# Servo_Control_Board.net
KiCad netlist of a schematic drawn in Altium Designer
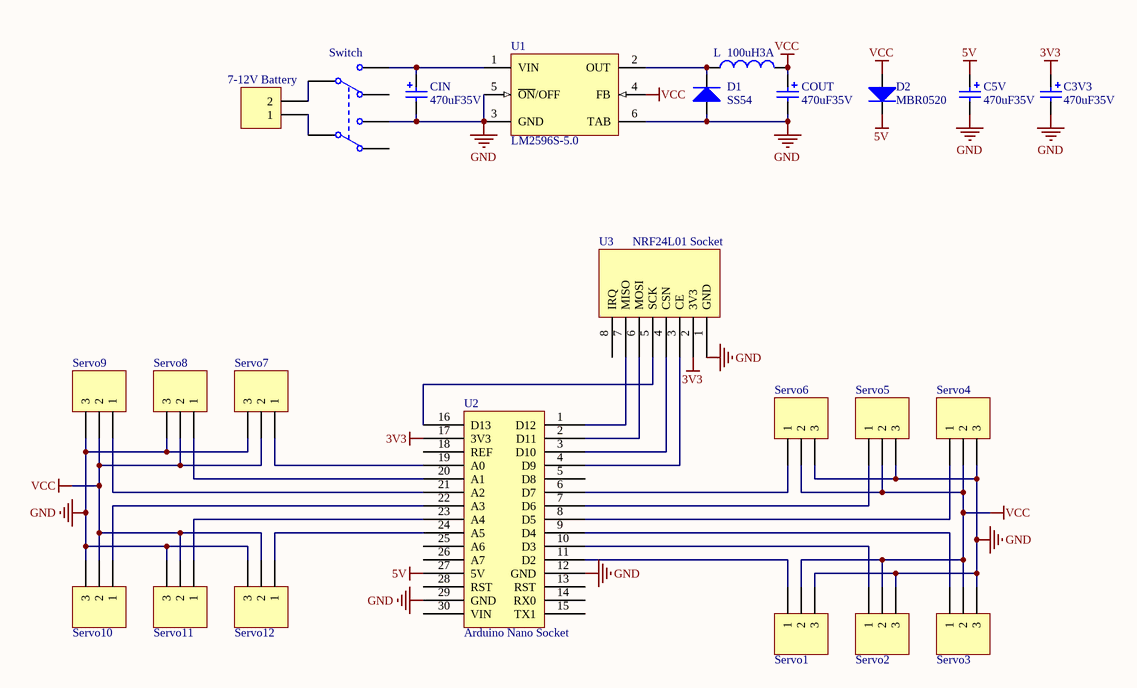
[diagram p0: Servo Control Board.SchDoc]

(export (version "E")
  (design (tool "Eeschema 10.0.6"))
  (components
    (comp (ref "7-12V Battery")
      (value "Header 2")
      (footprint "KF301-2P")
      (libsource (lib "Customer_Library") (part "Header 2"))
    )
    (comp (ref "C3V3")
      (value "470uF35V")
      (footprint "cp10x10")
      (fields (field (name "Comment") "Cap Pol"))
      (libsource (lib "Customer_Library") (part "Cap Pol"))
    )
    (comp (ref "C5V")
      (value "470uF35V")
      (footprint "cp10x10")
      (fields (field (name "Comment") "Cap Pol"))
      (libsource (lib "Customer_Library") (part "Cap Pol"))
    )
    (comp (ref "CIN")
      (value "470uF35V")
      (footprint "cp10x10")
      (fields (field (name "Comment") "Cap Pol"))
      (libsource (lib "Customer_Library") (part "Cap Pol"))
    )
    (comp (ref "COUT")
      (value "470uF35V")
      (footprint "cp10x10")
      (fields (field (name "Comment") "Cap Pol"))
      (libsource (lib "Customer_Library") (part "Cap Pol"))
    )
    (comp (ref "D1") (value "SS54") (footprint "SS54") (libsource (lib "Customer_Library") (part "Diode")))
    (comp (ref "D2")
      (value "MBR0520")
      (footprint "SOD-123")
      (libsource (lib "Customer_Library") (part "Diode"))
    )
    (comp (ref "L")
      (value "100uH3A")
      (footprint "Inductor 14.6x6.8x0.8")
      (fields (field (name "Comment") "Inductor"))
      (libsource (lib "Customer_Library") (part "Inductor"))
    )
    (comp (ref "Servo1") (value "Header 3") (footprint "Header 3") (libsource (lib "") (part "Header 3_3")))
    (comp (ref "Servo2") (value "Header 3") (footprint "Header 3") (libsource (lib "") (part "Header 3_3")))
    (comp (ref "Servo3") (value "Header 3") (footprint "Header 3") (libsource (lib "") (part "Header 3_3")))
    (comp (ref "Servo4")
      (value "Header 3")
      (footprint "Header 3")
      (libsource (lib "Customer_Library") (part "Header 3"))
    )
    (comp (ref "Servo5")
      (value "Header 3")
      (footprint "Header 3")
      (libsource (lib "Customer_Library") (part "Header 3"))
    )
    (comp (ref "Servo6")
      (value "Header 3")
      (footprint "Header 3")
      (libsource (lib "Customer_Library") (part "Header 3"))
    )
    (comp (ref "Servo7") (value "Header 3") (footprint "Header 3") (libsource (lib "") (part "Header 3_2")))
    (comp (ref "Servo8") (value "Header 3") (footprint "Header 3") (libsource (lib "") (part "Header 3_2")))
    (comp (ref "Servo9") (value "Header 3") (footprint "Header 3") (libsource (lib "") (part "Header 3_2")))
    (comp (ref "Servo10") (value "Header 3") (footprint "Header 3") (libsource (lib "") (part "Header 3_1")))
    (comp (ref "Servo11") (value "Header 3") (footprint "Header 3") (libsource (lib "") (part "Header 3_1")))
    (comp (ref "Servo12") (value "Header 3") (footprint "Header 3") (libsource (lib "") (part "Header 3_1")))
    (comp (ref "Switch")
      (value "Push Switch")
      (footprint "Push Switch 7x7")
      (libsource (lib "Customer_Library") (part "Push Switch"))
    )
    (comp (ref "U1")
      (value "LM2596S-5.0")
      (footprint "TS5B_N")
      (description "SIMPLE SWITCHER Power Converter 150 KHz 3A Step-Down Voltage Regulator")
      (fields
        (field (name "MANUFACTURER") "National Semiconductor")
        (field (name "DIGIKEYPARTNUMBER") "LM2596S-5.0-ND")
        (field (name "PUBLISHER") "Altium Limited")
      )
      (libsource (lib "NSC Switcher") (part "LM2596S-5.0"))
    )
    (comp (ref "U2")
      (value "Arduino Nano Socket")
      (footprint "arduino nano socket")
      (libsource (lib "Customer_Library") (part "Arduino Nano Socket"))
    )
    (comp (ref "U3")
      (value "NRF24L01 Socket")
      (footprint "nrf24l01 socket")
      (libsource (lib "Customer_Library") (part "NRF24L01 Socket"))
    )
  )
  (nets
    (net (code "1") (name "3V3") (class "Default")
      (node (ref "C3V3") (pin "1") (pinfunction "1_1") (pintype "passive"))
      (node (ref "U2") (pin "17") (pinfunction "3V3_17") (pintype "passive"))
      (node (ref "U3") (pin "2") (pinfunction "3V3_2") (pintype "passive"))
    )
    (net (code "2") (name "5V") (class "Default")
      (node (ref "C5V") (pin "1") (pinfunction "1_1") (pintype "passive"))
      (node (ref "D2") (pin "2") (pinfunction "K_2") (pintype "passive"))
      (node (ref "U2") (pin "27") (pinfunction "5V_27") (pintype "passive"))
    )
    (net (code "3") (name "GND") (class "Default")
      (node (ref "C3V3") (pin "2") (pinfunction "2_2") (pintype "passive"))
      (node (ref "C5V") (pin "2") (pinfunction "2_2") (pintype "passive"))
      (node (ref "CIN") (pin "2") (pinfunction "2_2") (pintype "passive"))
      (node (ref "COUT") (pin "2") (pinfunction "2_2") (pintype "passive"))
      (node (ref "D1") (pin "1") (pinfunction "A_1") (pintype "passive"))
      (node (ref "Servo1") (pin "3") (pinfunction "3_3") (pintype "passive"))
      (node (ref "Servo10") (pin "3") (pinfunction "3_3") (pintype "passive"))
      (node (ref "Servo11") (pin "3") (pinfunction "3_3") (pintype "passive"))
      (node (ref "Servo12") (pin "3") (pinfunction "3_3") (pintype "passive"))
      (node (ref "Servo2") (pin "3") (pinfunction "3_3") (pintype "passive"))
      (node (ref "Servo3") (pin "3") (pinfunction "3_3") (pintype "passive"))
      (node (ref "Servo4") (pin "3") (pinfunction "3_3") (pintype "passive"))
      (node (ref "Servo5") (pin "3") (pinfunction "3_3") (pintype "passive"))
      (node (ref "Servo6") (pin "3") (pinfunction "3_3") (pintype "passive"))
      (node (ref "Servo7") (pin "3") (pinfunction "3_3") (pintype "passive"))
      (node (ref "Servo8") (pin "3") (pinfunction "3_3") (pintype "passive"))
      (node (ref "Servo9") (pin "3") (pinfunction "3_3") (pintype "passive"))
      (node (ref "Switch") (pin "3") (pinfunction "NO1_3") (pintype "passive"))
      (node (ref "U1") (pin "3") (pinfunction "GND_3") (pintype "power_in"))
      (node (ref "U1") (pin "5") (pinfunction "~{ON}/OFF_5") (pintype "input"))
      (node (ref "U1") (pin "6") (pinfunction "TAB_6") (pintype "power_in"))
      (node (ref "U2") (pin "12") (pinfunction "GND_12") (pintype "passive"))
      (node (ref "U2") (pin "29") (pinfunction "GND_29") (pintype "passive"))
      (node (ref "U3") (pin "1") (pinfunction "GND_1") (pintype "passive"))
    )
    (net (code "4") (name "Net-(D1-K)") (class "Default")
      (node (ref "D1") (pin "2") (pinfunction "K_2") (pintype "passive"))
      (node (ref "L") (pin "1") (pinfunction "1_1") (pintype "passive"))
      (node (ref "U1") (pin "2") (pinfunction "OUT_2") (pintype "power_in"))
    )
    (net (code "5") (name "Net-(Switch-COMMON1)") (class "Default")
      (node (ref "7-12V Battery") (pin "1") (pinfunction "1_1") (pintype "passive"))
      (node (ref "Switch") (pin "1") (pinfunction "COMMON1_1") (pintype "passive"))
    )
    (net (code "6") (name "Net-(Switch-COMMON2)") (class "Default")
      (node (ref "7-12V Battery") (pin "2") (pinfunction "2_2") (pintype "passive"))
      (node (ref "Switch") (pin "4") (pinfunction "COMMON2_4") (pintype "passive"))
    )
    (net (code "7") (name "Net-(Switch-NO2)") (class "Default")
      (node (ref "CIN") (pin "1") (pinfunction "1_1") (pintype "passive"))
      (node (ref "Switch") (pin "6") (pinfunction "NO2_6") (pintype "passive"))
      (node (ref "U1") (pin "1") (pinfunction "VIN_1") (pintype "power_in"))
    )
    (net (code "8") (name "Net-(U2-A0)") (class "Default")
      (node (ref "Servo7") (pin "1") (pinfunction "1_1") (pintype "passive"))
      (node (ref "U2") (pin "19") (pinfunction "A0_19") (pintype "passive"))
    )
    (net (code "9") (name "Net-(U2-A1)") (class "Default")
      (node (ref "Servo8") (pin "1") (pinfunction "1_1") (pintype "passive"))
      (node (ref "U2") (pin "20") (pinfunction "A1_20") (pintype "passive"))
    )
    (net (code "10") (name "Net-(U2-A2)") (class "Default")
      (node (ref "Servo9") (pin "1") (pinfunction "1_1") (pintype "passive"))
      (node (ref "U2") (pin "21") (pinfunction "A2_21") (pintype "passive"))
    )
    (net (code "11") (name "Net-(U2-A3)") (class "Default")
      (node (ref "Servo10") (pin "1") (pinfunction "1_1") (pintype "passive"))
      (node (ref "U2") (pin "22") (pinfunction "A3_22") (pintype "passive"))
    )
    (net (code "12") (name "Net-(U2-A4)") (class "Default")
      (node (ref "Servo11") (pin "1") (pinfunction "1_1") (pintype "passive"))
      (node (ref "U2") (pin "23") (pinfunction "A4_23") (pintype "passive"))
    )
    (net (code "13") (name "Net-(U2-A5)") (class "Default")
      (node (ref "Servo12") (pin "1") (pinfunction "1_1") (pintype "passive"))
      (node (ref "U2") (pin "24") (pinfunction "A5_24") (pintype "passive"))
    )
    (net (code "14") (name "Net-(U2-D2)") (class "Default")
      (node (ref "Servo1") (pin "1") (pinfunction "1_1") (pintype "passive"))
      (node (ref "U2") (pin "11") (pinfunction "D2_11") (pintype "passive"))
    )
    (net (code "15") (name "Net-(U2-D3)") (class "Default")
      (node (ref "Servo2") (pin "1") (pinfunction "1_1") (pintype "passive"))
      (node (ref "U2") (pin "10") (pinfunction "D3_10") (pintype "passive"))
    )
    (net (code "16") (name "Net-(U2-D4)") (class "Default")
      (node (ref "Servo3") (pin "1") (pinfunction "1_1") (pintype "passive"))
      (node (ref "U2") (pin "9") (pinfunction "D4_9") (pintype "passive"))
    )
    (net (code "17") (name "Net-(U2-D5)") (class "Default")
      (node (ref "Servo4") (pin "1") (pinfunction "1_1") (pintype "passive"))
      (node (ref "U2") (pin "8") (pinfunction "D5_8") (pintype "passive"))
    )
    (net (code "18") (name "Net-(U2-D6)") (class "Default")
      (node (ref "Servo5") (pin "1") (pinfunction "1_1") (pintype "passive"))
      (node (ref "U2") (pin "7") (pinfunction "D6_7") (pintype "passive"))
    )
    (net (code "19") (name "Net-(U2-D7)") (class "Default")
      (node (ref "Servo6") (pin "1") (pinfunction "1_1") (pintype "passive"))
      (node (ref "U2") (pin "6") (pinfunction "D7_6") (pintype "passive"))
    )
    (net (code "20") (name "Net-(U2-D9)") (class "Default")
      (node (ref "U2") (pin "4") (pinfunction "D9_4") (pintype "passive"))
      (node (ref "U3") (pin "3") (pinfunction "CE_3") (pintype "passive"))
    )
    (net (code "21") (name "Net-(U2-D10)") (class "Default")
      (node (ref "U2") (pin "3") (pinfunction "D10_3") (pintype "passive"))
      (node (ref "U3") (pin "4") (pinfunction "CSN_4") (pintype "passive"))
    )
    (net (code "22") (name "Net-(U2-D11)") (class "Default")
      (node (ref "U2") (pin "2") (pinfunction "D11_2") (pintype "passive"))
      (node (ref "U3") (pin "6") (pinfunction "MOSI_6") (pintype "passive"))
    )
    (net (code "23") (name "Net-(U2-D12)") (class "Default")
      (node (ref "U2") (pin "1") (pinfunction "D12_1") (pintype "passive"))
      (node (ref "U3") (pin "7") (pinfunction "MISO_7") (pintype "passive"))
    )
    (net (code "24") (name "Net-(U2-D13)") (class "Default")
      (node (ref "U2") (pin "16") (pinfunction "D13_16") (pintype "passive"))
      (node (ref "U3") (pin "5") (pinfunction "SCK_5") (pintype "passive"))
    )
    (net (code "25") (name "VCC") (class "Default")
      (node (ref "COUT") (pin "1") (pinfunction "1_1") (pintype "passive"))
      (node (ref "D2") (pin "1") (pinfunction "A_1") (pintype "passive"))
      (node (ref "L") (pin "2") (pinfunction "2_2") (pintype "passive"))
      (node (ref "Servo1") (pin "2") (pinfunction "2_2") (pintype "passive"))
      (node (ref "Servo10") (pin "2") (pinfunction "2_2") (pintype "passive"))
      (node (ref "Servo11") (pin "2") (pinfunction "2_2") (pintype "passive"))
      (node (ref "Servo12") (pin "2") (pinfunction "2_2") (pintype "passive"))
      (node (ref "Servo2") (pin "2") (pinfunction "2_2") (pintype "passive"))
      (node (ref "Servo3") (pin "2") (pinfunction "2_2") (pintype "passive"))
      (node (ref "Servo4") (pin "2") (pinfunction "2_2") (pintype "passive"))
      (node (ref "Servo5") (pin "2") (pinfunction "2_2") (pintype "passive"))
      (node (ref "Servo6") (pin "2") (pinfunction "2_2") (pintype "passive"))
      (node (ref "Servo7") (pin "2") (pinfunction "2_2") (pintype "passive"))
      (node (ref "Servo8") (pin "2") (pinfunction "2_2") (pintype "passive"))
      (node (ref "Servo9") (pin "2") (pinfunction "2_2") (pintype "passive"))
      (node (ref "U1") (pin "4") (pinfunction "FB_4") (pintype "input"))
    )
    (net (code "26") (name "unconnected-(Switch-NC1-Pad2)") (class "Default")
      (node (ref "Switch") (pin "2") (pinfunction "NC1_2") (pintype "passive"))
    )
    (net (code "27") (name "unconnected-(Switch-NC2-Pad5)") (class "Default")
      (node (ref "Switch") (pin "5") (pinfunction "NC2_5") (pintype "passive"))
    )
    (net (code "28") (name "unconnected-(U2-A6-Pad25)") (class "Default")
      (node (ref "U2") (pin "25") (pinfunction "A6_25") (pintype "passive"))
    )
    (net (code "29") (name "unconnected-(U2-A7-Pad26)") (class "Default")
      (node (ref "U2") (pin "26") (pinfunction "A7_26") (pintype "passive"))
    )
    (net (code "30") (name "unconnected-(U2-D8-Pad5)") (class "Default")
      (node (ref "U2") (pin "5") (pinfunction "D8_5") (pintype "passive"))
    )
    (net (code "31") (name "unconnected-(U2-REF-Pad18)") (class "Default")
      (node (ref "U2") (pin "18") (pinfunction "REF_18") (pintype "passive"))
    )
    (net (code "32") (name "unconnected-(U2-RST-Pad13)") (class "Default")
      (node (ref "U2") (pin "13") (pinfunction "RST_13") (pintype "passive"))
    )
    (net (code "33") (name "unconnected-(U2-RST-Pad28)") (class "Default")
      (node (ref "U2") (pin "28") (pinfunction "RST_28") (pintype "passive"))
    )
    (net (code "34") (name "unconnected-(U2-RX0-Pad14)") (class "Default")
      (node (ref "U2") (pin "14") (pinfunction "RX0_14") (pintype "passive"))
    )
    (net (code "35") (name "unconnected-(U2-TX1-Pad15)") (class "Default")
      (node (ref "U2") (pin "15") (pinfunction "TX1_15") (pintype "passive"))
    )
    (net (code "36") (name "unconnected-(U2-VIN-Pad30)") (class "Default")
      (node (ref "U2") (pin "30") (pinfunction "VIN_30") (pintype "passive"))
    )
    (net (code "37") (name "unconnected-(U3-IRQ-Pad8)") (class "Default")
      (node (ref "U3") (pin "8") (pinfunction "IRQ_8") (pintype "passive"))
    )
  )
)
